# indication.net
KiCad netlist of a schematic drawn in Altium Designer
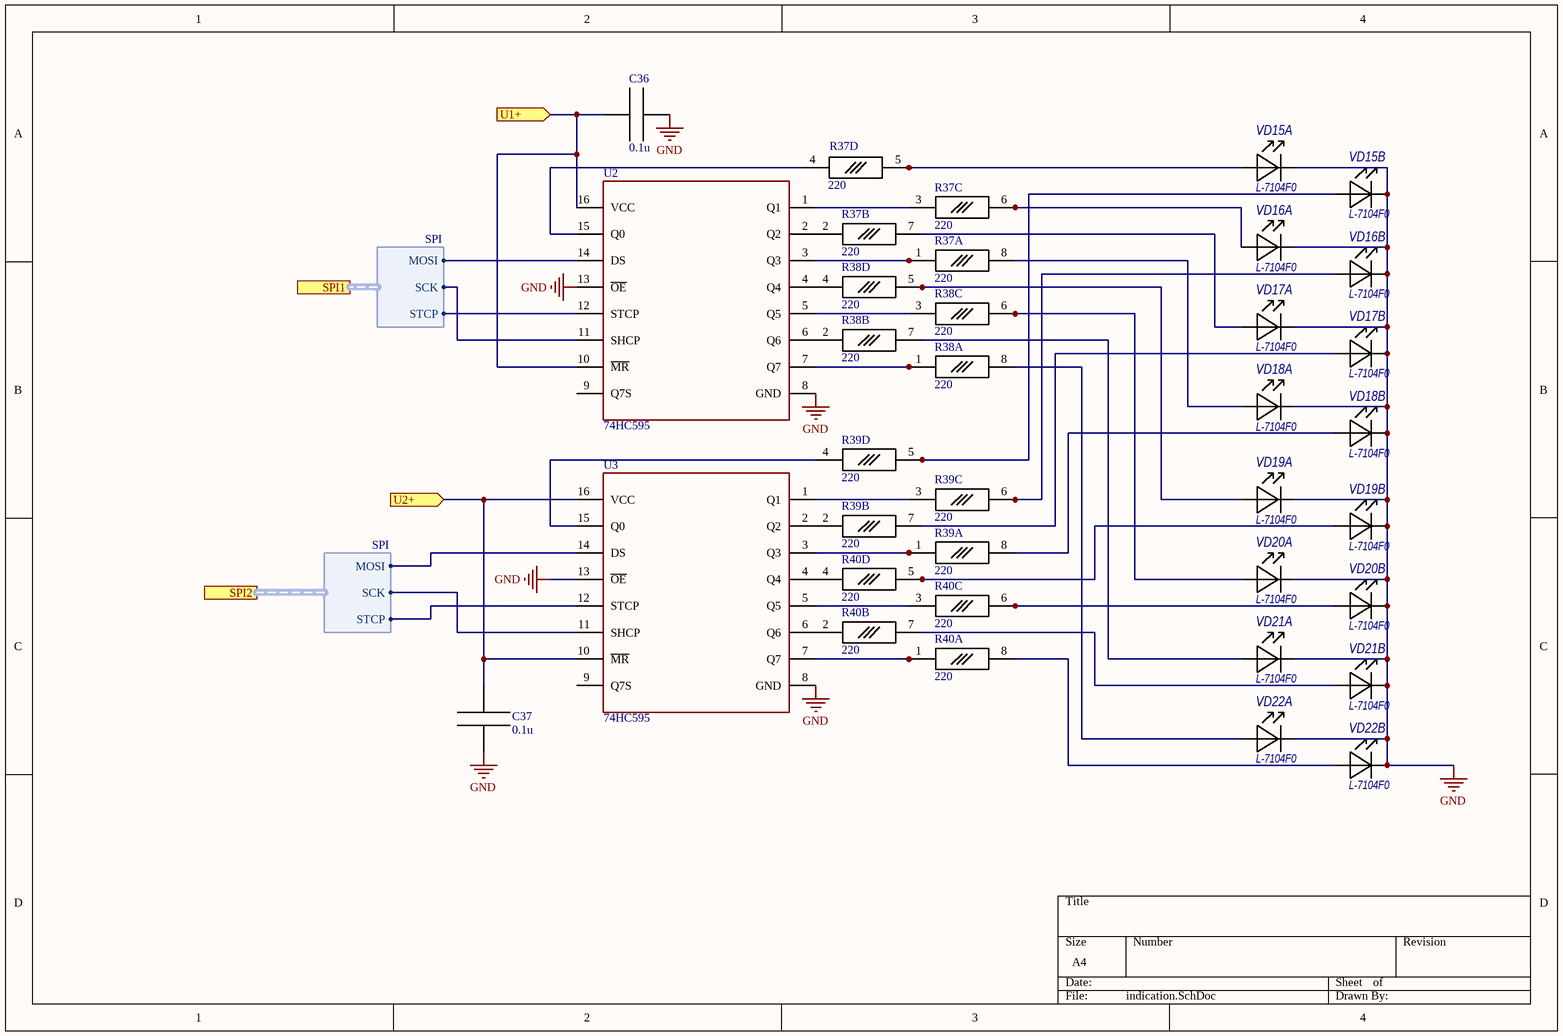
[diagram p0: indication.SchDoc]

(export (version "E")
  (design (tool "Eeschema 10.0.6"))
  (components
    (comp (ref "C36") (value "0.1u") (footprint "cap_0402") (libsource (lib "lib") (part "cap")))
    (comp (ref "C37") (value "0.1u") (footprint "cap_0402") (libsource (lib "lib") (part "cap")))
    (comp (ref "R37")
      (value "220")
      (footprint "YC164")
      (description "YC164")
      (libsource (lib "my_sch_lib") (part "res_array"))
    )
    (comp (ref "R38")
      (value "220")
      (footprint "YC164")
      (description "YC164")
      (libsource (lib "my_sch_lib") (part "res_array"))
    )
    (comp (ref "R39")
      (value "220")
      (footprint "YC164")
      (description "YC164")
      (libsource (lib "my_sch_lib") (part "res_array"))
    )
    (comp (ref "R40")
      (value "220")
      (footprint "YC164")
      (description "YC164")
      (libsource (lib "my_sch_lib") (part "res_array"))
    )
    (comp (ref "U2") (value "74HC595") (footprint "TSSOP16") (libsource (lib "lib") (part "74hc595")))
    (comp (ref "U3") (value "74HC595") (footprint "TSSOP16") (libsource (lib "lib") (part "74hc595")))
    (comp (ref "VD15")
      (value "Diod_sv_L-7104F0")
      (footprint "L-7104_")
      (fields (field (name "TYPE") "L-7104F0"))
      (libsource (lib "my_sch_lib") (part "Diod_sv_L-7104F0"))
    )
    (comp (ref "VD16")
      (value "Diod_sv_L-7104F0")
      (footprint "L-7104_")
      (fields (field (name "TYPE") "L-7104F0"))
      (libsource (lib "my_sch_lib") (part "Diod_sv_L-7104F0"))
    )
    (comp (ref "VD17")
      (value "Diod_sv_L-7104F0")
      (footprint "L-7104_")
      (fields (field (name "TYPE") "L-7104F0"))
      (libsource (lib "my_sch_lib") (part "Diod_sv_L-7104F0"))
    )
    (comp (ref "VD18")
      (value "Diod_sv_L-7104F0")
      (footprint "L-7104_")
      (fields (field (name "TYPE") "L-7104F0"))
      (libsource (lib "my_sch_lib") (part "Diod_sv_L-7104F0"))
    )
    (comp (ref "VD19")
      (value "Diod_sv_L-7104F0")
      (footprint "L-7104_")
      (fields (field (name "TYPE") "L-7104F0"))
      (libsource (lib "my_sch_lib") (part "Diod_sv_L-7104F0"))
    )
    (comp (ref "VD20")
      (value "Diod_sv_L-7104F0")
      (footprint "L-7104_")
      (fields (field (name "TYPE") "L-7104F0"))
      (libsource (lib "my_sch_lib") (part "Diod_sv_L-7104F0"))
    )
    (comp (ref "VD21")
      (value "Diod_sv_L-7104F0")
      (footprint "L-7104_")
      (fields (field (name "TYPE") "L-7104F0"))
      (libsource (lib "my_sch_lib") (part "Diod_sv_L-7104F0"))
    )
    (comp (ref "VD22")
      (value "Diod_sv_L-7104F0")
      (footprint "L-7104_")
      (fields (field (name "TYPE") "L-7104F0"))
      (libsource (lib "my_sch_lib") (part "Diod_sv_L-7104F0"))
    )
  )
  (nets
    (net (code "2") (name "/U1+") (class "Default")
      (node (ref "C36") (pin "1") (pinfunction "1_1") (pintype "passive"))
      (node (ref "U2") (pin "10") (pinfunction "~{MR}_10") (pintype "passive"))
      (node (ref "U2") (pin "16") (pinfunction "VCC_16") (pintype "passive"))
    )
    (net (code "3") (name "/U2+") (class "Default")
      (node (ref "C37") (pin "1") (pinfunction "1_1") (pintype "passive"))
      (node (ref "U3") (pin "10") (pinfunction "~{MR}_10") (pintype "passive"))
      (node (ref "U3") (pin "16") (pinfunction "VCC_16") (pintype "passive"))
    )
    (net (code "5") (name "GND") (class "Default")
      (node (ref "C36") (pin "2") (pinfunction "2_2") (pintype "passive"))
      (node (ref "C37") (pin "2") (pinfunction "2_2") (pintype "passive"))
      (node (ref "U2") (pin "13") (pinfunction "~{OE}_13") (pintype "passive"))
      (node (ref "U2") (pin "8") (pinfunction "GND_8") (pintype "passive"))
      (node (ref "U3") (pin "13") (pinfunction "~{OE}_13") (pintype "passive"))
      (node (ref "U3") (pin "8") (pinfunction "GND_8") (pintype "passive"))
      (node (ref "VD15") (pin "2") (pinfunction "K1_2") (pintype "passive"))
      (node (ref "VD15") (pin "4") (pinfunction "K2_4") (pintype "passive"))
      (node (ref "VD16") (pin "2") (pinfunction "K1_2") (pintype "passive"))
      (node (ref "VD16") (pin "4") (pinfunction "K2_4") (pintype "passive"))
      (node (ref "VD17") (pin "2") (pinfunction "K1_2") (pintype "passive"))
      (node (ref "VD17") (pin "4") (pinfunction "K2_4") (pintype "passive"))
      (node (ref "VD18") (pin "2") (pinfunction "K1_2") (pintype "passive"))
      (node (ref "VD18") (pin "4") (pinfunction "K2_4") (pintype "passive"))
      (node (ref "VD19") (pin "2") (pinfunction "K1_2") (pintype "passive"))
      (node (ref "VD19") (pin "4") (pinfunction "K2_4") (pintype "passive"))
      (node (ref "VD20") (pin "2") (pinfunction "K1_2") (pintype "passive"))
      (node (ref "VD20") (pin "4") (pinfunction "K2_4") (pintype "passive"))
      (node (ref "VD21") (pin "2") (pinfunction "K1_2") (pintype "passive"))
      (node (ref "VD21") (pin "4") (pinfunction "K2_4") (pintype "passive"))
      (node (ref "VD22") (pin "2") (pinfunction "K1_2") (pintype "passive"))
      (node (ref "VD22") (pin "4") (pinfunction "K2_4") (pintype "passive"))
    )
    (net (code "6") (name "Net-(U2-Q0)") (class "Default")
      (node (ref "R37") (pin "4") (pinfunction "4_4") (pintype "passive"))
      (node (ref "U2") (pin "15") (pinfunction "Q0_15") (pintype "passive"))
    )
    (net (code "7") (name "Net-(U2-Q1)") (class "Default")
      (node (ref "R37") (pin "3") (pinfunction "3_3") (pintype "passive"))
      (node (ref "U2") (pin "1") (pinfunction "Q1_1") (pintype "passive"))
    )
    (net (code "8") (name "Net-(U2-Q2)") (class "Default")
      (node (ref "R37") (pin "2") (pinfunction "2_2") (pintype "passive"))
      (node (ref "U2") (pin "2") (pinfunction "Q2_2") (pintype "passive"))
    )
    (net (code "9") (name "Net-(U2-Q3)") (class "Default")
      (node (ref "R37") (pin "1") (pinfunction "1_1") (pintype "passive"))
      (node (ref "U2") (pin "3") (pinfunction "Q3_3") (pintype "passive"))
    )
    (net (code "10") (name "Net-(U2-Q4)") (class "Default")
      (node (ref "R38") (pin "4") (pinfunction "4_4") (pintype "passive"))
      (node (ref "U2") (pin "4") (pinfunction "Q4_4") (pintype "passive"))
    )
    (net (code "11") (name "Net-(U2-Q5)") (class "Default")
      (node (ref "R38") (pin "3") (pinfunction "3_3") (pintype "passive"))
      (node (ref "U2") (pin "5") (pinfunction "Q5_5") (pintype "passive"))
    )
    (net (code "12") (name "Net-(U2-Q6)") (class "Default")
      (node (ref "R38") (pin "2") (pinfunction "2_2") (pintype "passive"))
      (node (ref "U2") (pin "6") (pinfunction "Q6_6") (pintype "passive"))
    )
    (net (code "13") (name "Net-(U2-Q7)") (class "Default")
      (node (ref "R38") (pin "1") (pinfunction "1_1") (pintype "passive"))
      (node (ref "U2") (pin "7") (pinfunction "Q7_7") (pintype "passive"))
    )
    (net (code "14") (name "Net-(U3-Q0)") (class "Default")
      (node (ref "R39") (pin "4") (pinfunction "4_4") (pintype "passive"))
      (node (ref "U3") (pin "15") (pinfunction "Q0_15") (pintype "passive"))
    )
    (net (code "15") (name "Net-(U3-Q1)") (class "Default")
      (node (ref "R39") (pin "3") (pinfunction "3_3") (pintype "passive"))
      (node (ref "U3") (pin "1") (pinfunction "Q1_1") (pintype "passive"))
    )
    (net (code "16") (name "Net-(U3-Q2)") (class "Default")
      (node (ref "R39") (pin "2") (pinfunction "2_2") (pintype "passive"))
      (node (ref "U3") (pin "2") (pinfunction "Q2_2") (pintype "passive"))
    )
    (net (code "17") (name "Net-(U3-Q3)") (class "Default")
      (node (ref "R39") (pin "1") (pinfunction "1_1") (pintype "passive"))
      (node (ref "U3") (pin "3") (pinfunction "Q3_3") (pintype "passive"))
    )
    (net (code "18") (name "Net-(U3-Q4)") (class "Default")
      (node (ref "R40") (pin "4") (pinfunction "4_4") (pintype "passive"))
      (node (ref "U3") (pin "4") (pinfunction "Q4_4") (pintype "passive"))
    )
    (net (code "19") (name "Net-(U3-Q5)") (class "Default")
      (node (ref "R40") (pin "3") (pinfunction "3_3") (pintype "passive"))
      (node (ref "U3") (pin "5") (pinfunction "Q5_5") (pintype "passive"))
    )
    (net (code "20") (name "Net-(U3-Q6)") (class "Default")
      (node (ref "R40") (pin "2") (pinfunction "2_2") (pintype "passive"))
      (node (ref "U3") (pin "6") (pinfunction "Q6_6") (pintype "passive"))
    )
    (net (code "21") (name "Net-(U3-Q7)") (class "Default")
      (node (ref "R40") (pin "1") (pinfunction "1_1") (pintype "passive"))
      (node (ref "U3") (pin "7") (pinfunction "Q7_7") (pintype "passive"))
    )
    (net (code "22") (name "Net-(VD15A-A1)") (class "Default")
      (node (ref "R37") (pin "5") (pinfunction "5_5") (pintype "passive"))
      (node (ref "VD15") (pin "1") (pinfunction "A1_1") (pintype "passive"))
    )
    (net (code "23") (name "Net-(VD15B-A2)") (class "Default")
      (node (ref "R39") (pin "5") (pinfunction "5_5") (pintype "passive"))
      (node (ref "VD15") (pin "3") (pinfunction "A2_3") (pintype "passive"))
    )
    (net (code "24") (name "Net-(VD16A-A1)") (class "Default")
      (node (ref "R37") (pin "6") (pinfunction "6_6") (pintype "passive"))
      (node (ref "VD16") (pin "1") (pinfunction "A1_1") (pintype "passive"))
    )
    (net (code "25") (name "Net-(VD16B-A2)") (class "Default")
      (node (ref "R39") (pin "6") (pinfunction "6_6") (pintype "passive"))
      (node (ref "VD16") (pin "3") (pinfunction "A2_3") (pintype "passive"))
    )
    (net (code "26") (name "Net-(VD17A-A1)") (class "Default")
      (node (ref "R37") (pin "7") (pinfunction "7_7") (pintype "passive"))
      (node (ref "VD17") (pin "1") (pinfunction "A1_1") (pintype "passive"))
    )
    (net (code "27") (name "Net-(VD17B-A2)") (class "Default")
      (node (ref "R39") (pin "7") (pinfunction "7_7") (pintype "passive"))
      (node (ref "VD17") (pin "3") (pinfunction "A2_3") (pintype "passive"))
    )
    (net (code "28") (name "Net-(VD18A-A1)") (class "Default")
      (node (ref "R37") (pin "8") (pinfunction "8_8") (pintype "passive"))
      (node (ref "VD18") (pin "1") (pinfunction "A1_1") (pintype "passive"))
    )
    (net (code "29") (name "Net-(VD18B-A2)") (class "Default")
      (node (ref "R39") (pin "8") (pinfunction "8_8") (pintype "passive"))
      (node (ref "VD18") (pin "3") (pinfunction "A2_3") (pintype "passive"))
    )
    (net (code "30") (name "Net-(VD19A-A1)") (class "Default")
      (node (ref "R38") (pin "5") (pinfunction "5_5") (pintype "passive"))
      (node (ref "VD19") (pin "1") (pinfunction "A1_1") (pintype "passive"))
    )
    (net (code "31") (name "Net-(VD19B-A2)") (class "Default")
      (node (ref "R40") (pin "5") (pinfunction "5_5") (pintype "passive"))
      (node (ref "VD19") (pin "3") (pinfunction "A2_3") (pintype "passive"))
    )
    (net (code "32") (name "Net-(VD20A-A1)") (class "Default")
      (node (ref "R38") (pin "6") (pinfunction "6_6") (pintype "passive"))
      (node (ref "VD20") (pin "1") (pinfunction "A1_1") (pintype "passive"))
    )
    (net (code "33") (name "Net-(VD20B-A2)") (class "Default")
      (node (ref "R40") (pin "6") (pinfunction "6_6") (pintype "passive"))
      (node (ref "VD20") (pin "3") (pinfunction "A2_3") (pintype "passive"))
    )
    (net (code "34") (name "Net-(VD21A-A1)") (class "Default")
      (node (ref "R38") (pin "7") (pinfunction "7_7") (pintype "passive"))
      (node (ref "VD21") (pin "1") (pinfunction "A1_1") (pintype "passive"))
    )
    (net (code "35") (name "Net-(VD21B-A2)") (class "Default")
      (node (ref "R40") (pin "7") (pinfunction "7_7") (pintype "passive"))
      (node (ref "VD21") (pin "3") (pinfunction "A2_3") (pintype "passive"))
    )
    (net (code "36") (name "Net-(VD22A-A1)") (class "Default")
      (node (ref "R38") (pin "8") (pinfunction "8_8") (pintype "passive"))
      (node (ref "VD22") (pin "1") (pinfunction "A1_1") (pintype "passive"))
    )
    (net (code "37") (name "Net-(VD22B-A2)") (class "Default")
      (node (ref "R40") (pin "8") (pinfunction "8_8") (pintype "passive"))
      (node (ref "VD22") (pin "3") (pinfunction "A2_3") (pintype "passive"))
    )
    (net (code "38") (name "unconnected-(U2-DS-Pad14)") (class "Default")
      (node (ref "U2") (pin "14") (pinfunction "DS_14") (pintype "passive"))
    )
    (net (code "39") (name "unconnected-(U2-Q7S-Pad9)") (class "Default")
      (node (ref "U2") (pin "9") (pinfunction "Q7S_9") (pintype "passive"))
    )
    (net (code "40") (name "unconnected-(U2-SHCP-Pad11)") (class "Default")
      (node (ref "U2") (pin "11") (pinfunction "SHCP_11") (pintype "passive"))
    )
    (net (code "41") (name "unconnected-(U2-STCP-Pad12)") (class "Default")
      (node (ref "U2") (pin "12") (pinfunction "STCP_12") (pintype "passive"))
    )
    (net (code "42") (name "unconnected-(U3-DS-Pad14)") (class "Default")
      (node (ref "U3") (pin "14") (pinfunction "DS_14") (pintype "passive"))
    )
    (net (code "43") (name "unconnected-(U3-Q7S-Pad9)") (class "Default")
      (node (ref "U3") (pin "9") (pinfunction "Q7S_9") (pintype "passive"))
    )
    (net (code "44") (name "unconnected-(U3-SHCP-Pad11)") (class "Default")
      (node (ref "U3") (pin "11") (pinfunction "SHCP_11") (pintype "passive"))
    )
    (net (code "45") (name "unconnected-(U3-STCP-Pad12)") (class "Default")
      (node (ref "U3") (pin "12") (pinfunction "STCP_12") (pintype "passive"))
    )
  )
)
